# FredT232H_Board.net
KiCad netlist of a schematic drawn in EAGLE
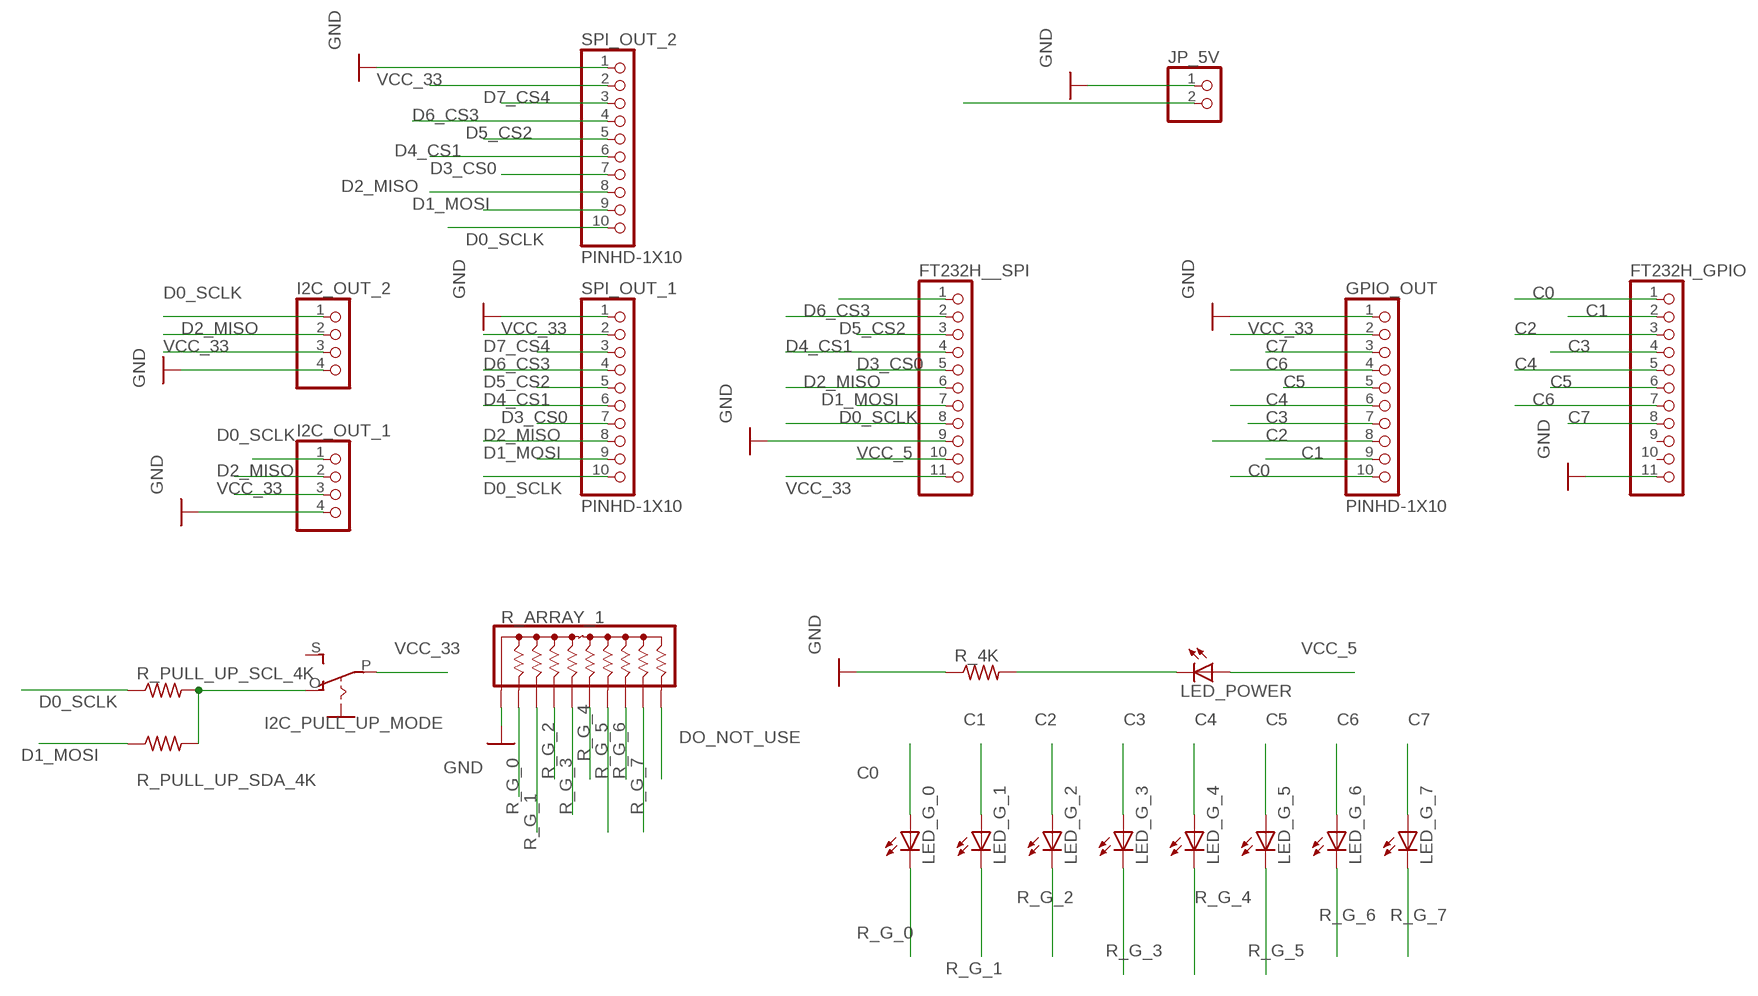
[diagram p0: schematic, sheet 1]

(export (version "E")
  (design (tool "Eeschema 10.0.6"))
  (components
    (comp (ref "FT232H_GPIO")
      (value "PINHD-1X11")
      (footprint "eagle-import:1X11")
      (libsource (lib "eagle-import") (part "PINHD-1X11"))
    )
    (comp (ref "FT232H__SPI")
      (value "PINHD-1X11")
      (footprint "eagle-import:1X11")
      (libsource (lib "eagle-import") (part "PINHD-1X11"))
    )
    (comp (ref "GPIO_OUT")
      (value "PINHD-1X10")
      (footprint "eagle-import:1X10-BIG")
      (libsource (lib "eagle-import") (part "PINHD-1X10"))
    )
    (comp (ref "I2C_OUT_1")
      (value "PINHD-1X4")
      (footprint "eagle-import:1X04")
      (libsource (lib "eagle-import") (part "PINHD-1X4"))
    )
    (comp (ref "I2C_OUT_2")
      (value "PINHD-1X4")
      (footprint "eagle-import:1X04")
      (libsource (lib "eagle-import") (part "PINHD-1X4"))
    )
    (comp (ref "I2C_PULL_UP_MODE")
      (value "EG1218S")
      (footprint "eagle-import:EG1218")
      (libsource (lib "eagle-import") (part "EG1218S"))
    )
    (comp (ref "JP_5V")
      (value "PINHD-1X2")
      (footprint "eagle-import:1X02")
      (libsource (lib "eagle-import") (part "PINHD-1X2"))
    )
    (comp (ref "LED_G_0")
      (value "LEDSMT1206")
      (footprint "eagle-import:1206")
      (libsource (lib "eagle-import") (part "LEDSMT1206"))
    )
    (comp (ref "LED_G_1")
      (value "LEDSMT1206")
      (footprint "eagle-import:1206")
      (libsource (lib "eagle-import") (part "LEDSMT1206"))
    )
    (comp (ref "LED_G_2")
      (value "LEDSMT1206")
      (footprint "eagle-import:1206")
      (libsource (lib "eagle-import") (part "LEDSMT1206"))
    )
    (comp (ref "LED_G_3")
      (value "LEDSMT1206")
      (footprint "eagle-import:1206")
      (libsource (lib "eagle-import") (part "LEDSMT1206"))
    )
    (comp (ref "LED_G_4")
      (value "LEDSMT1206")
      (footprint "eagle-import:1206")
      (libsource (lib "eagle-import") (part "LEDSMT1206"))
    )
    (comp (ref "LED_G_5")
      (value "LEDSMT1206")
      (footprint "eagle-import:1206")
      (libsource (lib "eagle-import") (part "LEDSMT1206"))
    )
    (comp (ref "LED_G_6")
      (value "LEDSMT1206")
      (footprint "eagle-import:1206")
      (libsource (lib "eagle-import") (part "LEDSMT1206"))
    )
    (comp (ref "LED_G_7")
      (value "LEDSMT1206")
      (footprint "eagle-import:1206")
      (libsource (lib "eagle-import") (part "LEDSMT1206"))
    )
    (comp (ref "LED_POWER")
      (value "LEDSMT1206")
      (footprint "eagle-import:1206")
      (libsource (lib "eagle-import") (part "LEDSMT1206"))
    )
    (comp (ref "R_4K")
      (value "R-US_R1206")
      (footprint "eagle-import:R1206")
      (libsource (lib "eagle-import") (part "R-US_R1206"))
    )
    (comp (ref "R_ARRAY_1")
      (value "4610X")
      (footprint "eagle-import:SIP10")
      (libsource (lib "eagle-import") (part "4610X"))
    )
    (comp (ref "R_PULL_UP_SCL_4K")
      (value "R-US_R1206")
      (footprint "eagle-import:R1206")
      (libsource (lib "eagle-import") (part "R-US_R1206"))
    )
    (comp (ref "R_PULL_UP_SDA_4K")
      (value "R-US_R1206")
      (footprint "eagle-import:R1206")
      (libsource (lib "eagle-import") (part "R-US_R1206"))
    )
    (comp (ref "SPI_OUT_1")
      (value "PINHD-1X10")
      (footprint "eagle-import:1X10-BIG")
      (libsource (lib "eagle-import") (part "PINHD-1X10"))
    )
    (comp (ref "SPI_OUT_2")
      (value "PINHD-1X10")
      (footprint "eagle-import:1X10-BIG")
      (libsource (lib "eagle-import") (part "PINHD-1X10"))
    )
  )
  (nets
    (net (code "1") (name "/C0") (class "Default")
      (node (ref "FT232H_GPIO") (pin "1") (pinfunction "1_1") (pintype "passive"))
      (node (ref "GPIO_OUT") (pin "10") (pinfunction "10_10") (pintype "passive"))
      (node (ref "LED_G_0") (pin "A") (pinfunction "A_A") (pintype "passive"))
    )
    (net (code "2") (name "/C1") (class "Default")
      (node (ref "FT232H_GPIO") (pin "2") (pinfunction "2_2") (pintype "passive"))
      (node (ref "GPIO_OUT") (pin "9") (pinfunction "9_9") (pintype "passive"))
      (node (ref "LED_G_1") (pin "A") (pinfunction "A_A") (pintype "passive"))
    )
    (net (code "3") (name "/C2") (class "Default")
      (node (ref "FT232H_GPIO") (pin "3") (pinfunction "3_3") (pintype "passive"))
      (node (ref "GPIO_OUT") (pin "8") (pinfunction "8_8") (pintype "passive"))
      (node (ref "LED_G_2") (pin "A") (pinfunction "A_A") (pintype "passive"))
    )
    (net (code "4") (name "/C3") (class "Default")
      (node (ref "FT232H_GPIO") (pin "4") (pinfunction "4_4") (pintype "passive"))
      (node (ref "GPIO_OUT") (pin "7") (pinfunction "7_7") (pintype "passive"))
      (node (ref "LED_G_3") (pin "A") (pinfunction "A_A") (pintype "passive"))
    )
    (net (code "5") (name "/C4") (class "Default")
      (node (ref "FT232H_GPIO") (pin "5") (pinfunction "5_5") (pintype "passive"))
      (node (ref "GPIO_OUT") (pin "6") (pinfunction "6_6") (pintype "passive"))
      (node (ref "LED_G_4") (pin "A") (pinfunction "A_A") (pintype "passive"))
    )
    (net (code "6") (name "/C5") (class "Default")
      (node (ref "FT232H_GPIO") (pin "6") (pinfunction "6_6") (pintype "passive"))
      (node (ref "GPIO_OUT") (pin "5") (pinfunction "5_5") (pintype "passive"))
      (node (ref "LED_G_5") (pin "A") (pinfunction "A_A") (pintype "passive"))
    )
    (net (code "7") (name "/C6") (class "Default")
      (node (ref "FT232H_GPIO") (pin "7") (pinfunction "7_7") (pintype "passive"))
      (node (ref "GPIO_OUT") (pin "4") (pinfunction "4_4") (pintype "passive"))
      (node (ref "LED_G_6") (pin "A") (pinfunction "A_A") (pintype "passive"))
    )
    (net (code "8") (name "/C7") (class "Default")
      (node (ref "FT232H_GPIO") (pin "8") (pinfunction "8_8") (pintype "passive"))
      (node (ref "GPIO_OUT") (pin "3") (pinfunction "3_3") (pintype "passive"))
      (node (ref "LED_G_7") (pin "A") (pinfunction "A_A") (pintype "passive"))
    )
    (net (code "9") (name "/D0_SCLK") (class "Default")
      (node (ref "FT232H__SPI") (pin "8") (pinfunction "8_8") (pintype "passive"))
      (node (ref "I2C_OUT_1") (pin "1") (pinfunction "1_1") (pintype "passive"))
      (node (ref "I2C_OUT_2") (pin "1") (pinfunction "1_1") (pintype "passive"))
      (node (ref "R_PULL_UP_SCL_4K") (pin "1") (pinfunction "1_1") (pintype "passive"))
      (node (ref "SPI_OUT_1") (pin "10") (pinfunction "10_10") (pintype "passive"))
      (node (ref "SPI_OUT_2") (pin "10") (pinfunction "10_10") (pintype "passive"))
    )
    (net (code "10") (name "/D1_MOSI") (class "Default")
      (node (ref "FT232H__SPI") (pin "7") (pinfunction "7_7") (pintype "passive"))
      (node (ref "R_PULL_UP_SDA_4K") (pin "1") (pinfunction "1_1") (pintype "passive"))
      (node (ref "SPI_OUT_1") (pin "9") (pinfunction "9_9") (pintype "passive"))
      (node (ref "SPI_OUT_2") (pin "9") (pinfunction "9_9") (pintype "passive"))
    )
    (net (code "11") (name "/D2_MISO") (class "Default")
      (node (ref "FT232H__SPI") (pin "6") (pinfunction "6_6") (pintype "passive"))
      (node (ref "I2C_OUT_1") (pin "2") (pinfunction "2_2") (pintype "passive"))
      (node (ref "I2C_OUT_2") (pin "2") (pinfunction "2_2") (pintype "passive"))
      (node (ref "SPI_OUT_1") (pin "8") (pinfunction "8_8") (pintype "passive"))
      (node (ref "SPI_OUT_2") (pin "8") (pinfunction "8_8") (pintype "passive"))
    )
    (net (code "12") (name "/D3_CS0") (class "Default")
      (node (ref "FT232H__SPI") (pin "5") (pinfunction "5_5") (pintype "passive"))
      (node (ref "SPI_OUT_1") (pin "7") (pinfunction "7_7") (pintype "passive"))
      (node (ref "SPI_OUT_2") (pin "7") (pinfunction "7_7") (pintype "passive"))
    )
    (net (code "13") (name "/D4_CS1") (class "Default")
      (node (ref "FT232H__SPI") (pin "4") (pinfunction "4_4") (pintype "passive"))
      (node (ref "SPI_OUT_1") (pin "6") (pinfunction "6_6") (pintype "passive"))
      (node (ref "SPI_OUT_2") (pin "6") (pinfunction "6_6") (pintype "passive"))
    )
    (net (code "14") (name "/D5_CS2") (class "Default")
      (node (ref "FT232H__SPI") (pin "3") (pinfunction "3_3") (pintype "passive"))
      (node (ref "SPI_OUT_1") (pin "5") (pinfunction "5_5") (pintype "passive"))
      (node (ref "SPI_OUT_2") (pin "5") (pinfunction "5_5") (pintype "passive"))
    )
    (net (code "15") (name "/D6_CS3") (class "Default")
      (node (ref "FT232H__SPI") (pin "2") (pinfunction "2_2") (pintype "passive"))
      (node (ref "SPI_OUT_1") (pin "4") (pinfunction "4_4") (pintype "passive"))
      (node (ref "SPI_OUT_2") (pin "4") (pinfunction "4_4") (pintype "passive"))
    )
    (net (code "16") (name "/D7_CS4") (class "Default")
      (node (ref "FT232H__SPI") (pin "1") (pinfunction "1_1") (pintype "passive"))
      (node (ref "SPI_OUT_1") (pin "3") (pinfunction "3_3") (pintype "passive"))
      (node (ref "SPI_OUT_2") (pin "3") (pinfunction "3_3") (pintype "passive"))
    )
    (net (code "17") (name "/DO_NOT_USE") (class "Default")
      (node (ref "R_ARRAY_1") (pin "10") (pinfunction "10_10") (pintype "passive"))
    )
    (net (code "18") (name "/R_G_0") (class "Default")
      (node (ref "LED_G_0") (pin "C") (pinfunction "C_C") (pintype "passive"))
      (node (ref "R_ARRAY_1") (pin "2") (pinfunction "2_2") (pintype "passive"))
    )
    (net (code "19") (name "/R_G_1") (class "Default")
      (node (ref "LED_G_1") (pin "C") (pinfunction "C_C") (pintype "passive"))
      (node (ref "R_ARRAY_1") (pin "3") (pinfunction "3_3") (pintype "passive"))
    )
    (net (code "20") (name "/R_G_2") (class "Default")
      (node (ref "LED_G_2") (pin "C") (pinfunction "C_C") (pintype "passive"))
      (node (ref "R_ARRAY_1") (pin "4") (pinfunction "4_4") (pintype "passive"))
    )
    (net (code "21") (name "/R_G_3") (class "Default")
      (node (ref "LED_G_3") (pin "C") (pinfunction "C_C") (pintype "passive"))
      (node (ref "R_ARRAY_1") (pin "5") (pinfunction "5_5") (pintype "passive"))
    )
    (net (code "22") (name "/R_G_4") (class "Default")
      (node (ref "LED_G_4") (pin "C") (pinfunction "C_C") (pintype "passive"))
      (node (ref "R_ARRAY_1") (pin "6") (pinfunction "6_6") (pintype "passive"))
    )
    (net (code "23") (name "/R_G_5") (class "Default")
      (node (ref "LED_G_5") (pin "C") (pinfunction "C_C") (pintype "passive"))
      (node (ref "R_ARRAY_1") (pin "7") (pinfunction "7_7") (pintype "passive"))
    )
    (net (code "24") (name "/R_G_6") (class "Default")
      (node (ref "LED_G_6") (pin "C") (pinfunction "C_C") (pintype "passive"))
      (node (ref "R_ARRAY_1") (pin "8") (pinfunction "8_8") (pintype "passive"))
    )
    (net (code "25") (name "/R_G_7") (class "Default")
      (node (ref "LED_G_7") (pin "C") (pinfunction "C_C") (pintype "passive"))
      (node (ref "R_ARRAY_1") (pin "9") (pinfunction "9_9") (pintype "passive"))
    )
    (net (code "26") (name "/VCC_5") (class "Default")
      (node (ref "FT232H__SPI") (pin "10") (pinfunction "10_10") (pintype "passive"))
      (node (ref "JP_5V") (pin "2") (pinfunction "2_2") (pintype "passive"))
      (node (ref "LED_POWER") (pin "A") (pinfunction "A_A") (pintype "passive"))
    )
    (net (code "27") (name "/VCC_33") (class "Default")
      (node (ref "FT232H__SPI") (pin "11") (pinfunction "11_11") (pintype "passive"))
      (node (ref "GPIO_OUT") (pin "2") (pinfunction "2_2") (pintype "passive"))
      (node (ref "I2C_OUT_1") (pin "3") (pinfunction "3_3") (pintype "passive"))
      (node (ref "I2C_OUT_2") (pin "3") (pinfunction "3_3") (pintype "passive"))
      (node (ref "I2C_PULL_UP_MODE") (pin "P") (pinfunction "P_P") (pintype "passive"))
      (node (ref "SPI_OUT_1") (pin "2") (pinfunction "2_2") (pintype "passive"))
      (node (ref "SPI_OUT_2") (pin "2") (pinfunction "2_2") (pintype "passive"))
    )
    (net (code "28") (name "GND") (class "Default")
      (node (ref "FT232H_GPIO") (pin "11") (pinfunction "11_11") (pintype "passive"))
      (node (ref "FT232H__SPI") (pin "9") (pinfunction "9_9") (pintype "passive"))
      (node (ref "GPIO_OUT") (pin "1") (pinfunction "1_1") (pintype "passive"))
      (node (ref "I2C_OUT_1") (pin "4") (pinfunction "4_4") (pintype "passive"))
      (node (ref "I2C_OUT_2") (pin "4") (pinfunction "4_4") (pintype "passive"))
      (node (ref "JP_5V") (pin "1") (pinfunction "1_1") (pintype "passive"))
      (node (ref "R_4K") (pin "1") (pinfunction "1_1") (pintype "passive"))
      (node (ref "R_ARRAY_1") (pin "1") (pinfunction "1_1") (pintype "passive"))
      (node (ref "SPI_OUT_1") (pin "1") (pinfunction "1_1") (pintype "passive"))
      (node (ref "SPI_OUT_2") (pin "1") (pinfunction "1_1") (pintype "passive"))
    )
    (net (code "29") (name "Net-(I2C_PULL_UP_MODE-PadO)") (class "Default")
      (node (ref "I2C_PULL_UP_MODE") (pin "O") (pinfunction "O_O") (pintype "passive"))
      (node (ref "R_PULL_UP_SCL_4K") (pin "2") (pinfunction "2_2") (pintype "passive"))
      (node (ref "R_PULL_UP_SDA_4K") (pin "2") (pinfunction "2_2") (pintype "passive"))
    )
    (net (code "30") (name "Net-(LED_POWER-PadC)") (class "Default")
      (node (ref "LED_POWER") (pin "C") (pinfunction "C_C") (pintype "passive"))
      (node (ref "R_4K") (pin "2") (pinfunction "2_2") (pintype "passive"))
    )
    (net (code "31") (name "unconnected-(FT232H_GPIO-Pad9)") (class "Default")
      (node (ref "FT232H_GPIO") (pin "9") (pinfunction "9_9") (pintype "passive"))
    )
    (net (code "32") (name "unconnected-(FT232H_GPIO-Pad10)") (class "Default")
      (node (ref "FT232H_GPIO") (pin "10") (pinfunction "10_10") (pintype "passive"))
    )
    (net (code "33") (name "unconnected-(I2C_PULL_UP_MODE-PadS)") (class "Default")
      (node (ref "I2C_PULL_UP_MODE") (pin "S") (pinfunction "S_S") (pintype "passive"))
    )
  )
)
